# Outputs.net
KiCad netlist of a schematic drawn in Altium Designer
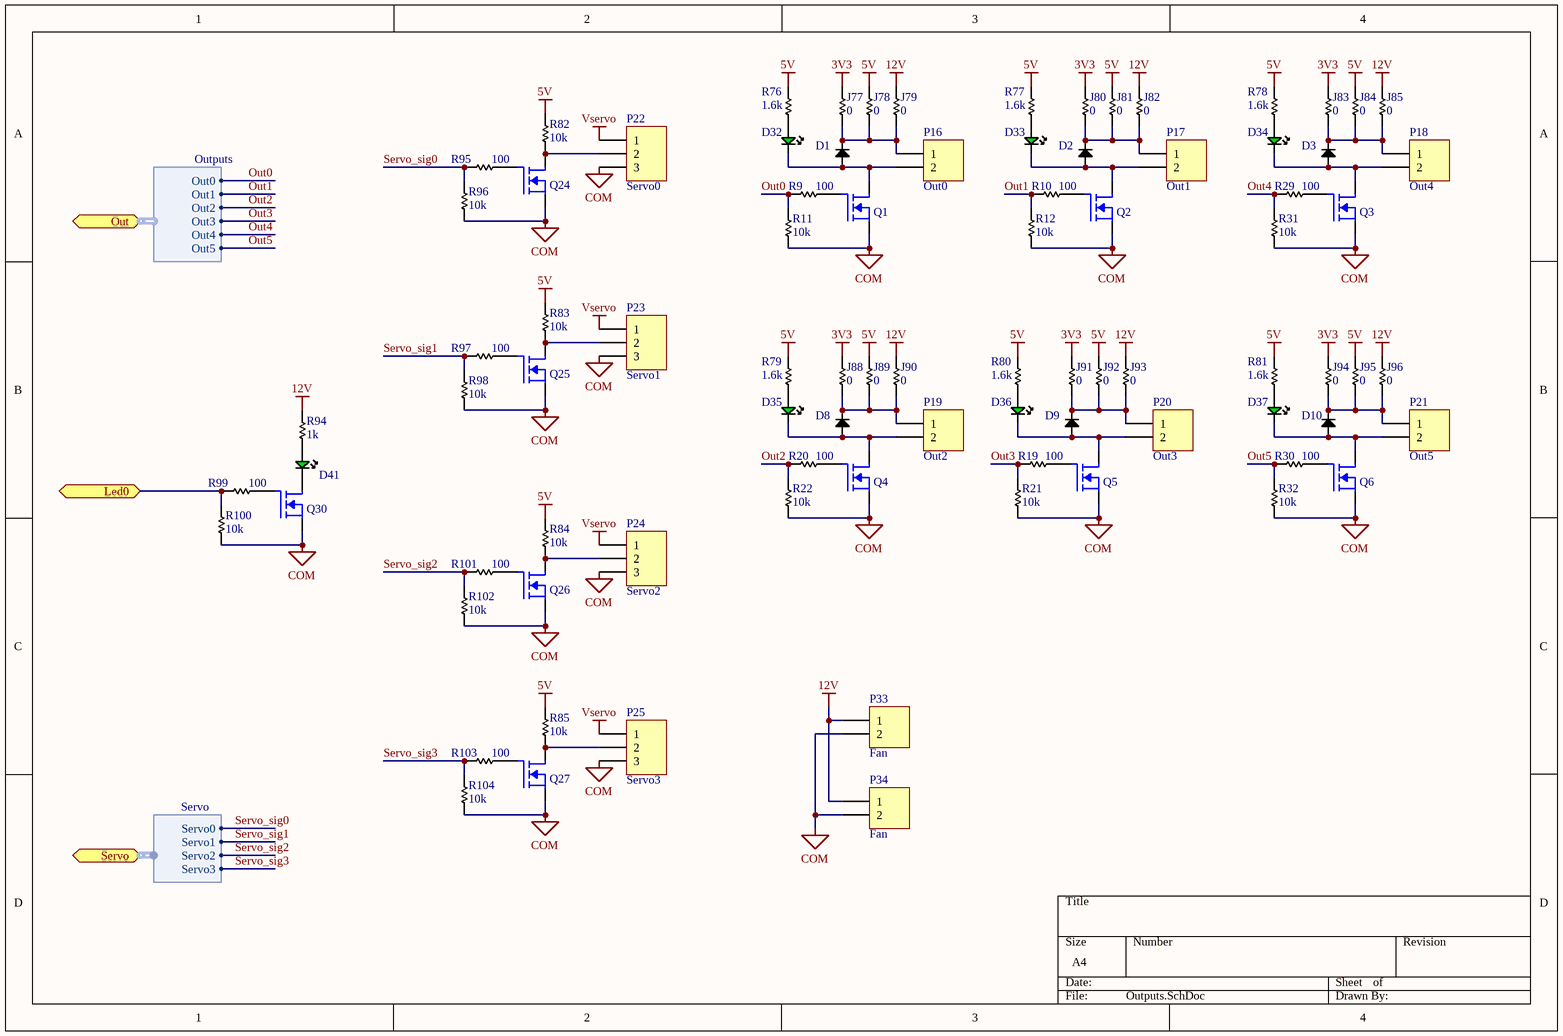
[diagram p0: Outputs.SchDoc]

(export (version "E")
  (design (tool "Eeschema 10.0.6"))
  (components
    (comp (ref "D1")
      (value "Diode")
      (footprint "DOS-214AC (SMA)")
      (description "DIODE GEN PURPOSE 1000V 1A SMA")
      (fields
        (field (name "PART NUMBER") "S1M-13-F")
        (field (name "MANUFACTURER") "Diodes Inc.")
        (field (name "CREATED BY") "Pier-Yves")
      )
      (libsource (lib "local") (part "Diode"))
    )
    (comp (ref "D2")
      (value "Diode")
      (footprint "DOS-214AC (SMA)")
      (description "DIODE GEN PURPOSE 1000V 1A SMA")
      (fields
        (field (name "PART NUMBER") "S1M-13-F")
        (field (name "MANUFACTURER") "Diodes Inc.")
        (field (name "CREATED BY") "Pier-Yves")
      )
      (libsource (lib "local") (part "Diode"))
    )
    (comp (ref "D3")
      (value "Diode")
      (footprint "DOS-214AC (SMA)")
      (description "DIODE GEN PURPOSE 1000V 1A SMA")
      (fields
        (field (name "PART NUMBER") "S1M-13-F")
        (field (name "MANUFACTURER") "Diodes Inc.")
        (field (name "CREATED BY") "Pier-Yves")
      )
      (libsource (lib "local") (part "Diode"))
    )
    (comp (ref "D8")
      (value "Diode")
      (footprint "DOS-214AC (SMA)")
      (description "DIODE GEN PURPOSE 1000V 1A SMA")
      (fields
        (field (name "PART NUMBER") "S1M-13-F")
        (field (name "MANUFACTURER") "Diodes Inc.")
        (field (name "CREATED BY") "Pier-Yves")
      )
      (libsource (lib "local") (part "Diode"))
    )
    (comp (ref "D9")
      (value "Diode")
      (footprint "DOS-214AC (SMA)")
      (description "DIODE GEN PURPOSE 1000V 1A SMA")
      (fields
        (field (name "PART NUMBER") "S1M-13-F")
        (field (name "MANUFACTURER") "Diodes Inc.")
        (field (name "CREATED BY") "Pier-Yves")
      )
      (libsource (lib "local") (part "Diode"))
    )
    (comp (ref "D10")
      (value "Diode")
      (footprint "DOS-214AC (SMA)")
      (description "DIODE GEN PURPOSE 1000V 1A SMA")
      (fields
        (field (name "PART NUMBER") "S1M-13-F")
        (field (name "MANUFACTURER") "Diodes Inc.")
        (field (name "CREATED BY") "Pier-Yves")
      )
      (libsource (lib "local") (part "Diode"))
    )
    (comp (ref "D32")
      (value "Green")
      (footprint "0603 - Led Green")
      (description "LED SMARTLED GREEN 570NM 0603")
      (fields
        (field (name "PART NUMBER") "LED-Green-2mA-lowBrigthness-0603")
        (field (name "MANUFACTURER") "OSRAM Opto Semiconductor")
        (field (name "CREATED BY") "Pier-Yves")
      )
      (libsource (lib "local") (part "Led Green"))
    )
    (comp (ref "D33")
      (value "Green")
      (footprint "0603 - Led Green")
      (description "LED SMARTLED GREEN 570NM 0603")
      (fields
        (field (name "PART NUMBER") "LED-Green-2mA-lowBrigthness-0603")
        (field (name "MANUFACTURER") "OSRAM Opto Semiconductor")
        (field (name "CREATED BY") "Pier-Yves")
      )
      (libsource (lib "local") (part "Led Green"))
    )
    (comp (ref "D34")
      (value "Green")
      (footprint "0603 - Led Green")
      (description "LED SMARTLED GREEN 570NM 0603")
      (fields
        (field (name "PART NUMBER") "LED-Green-2mA-lowBrigthness-0603")
        (field (name "MANUFACTURER") "OSRAM Opto Semiconductor")
        (field (name "CREATED BY") "Pier-Yves")
      )
      (libsource (lib "local") (part "Led Green"))
    )
    (comp (ref "D35")
      (value "Green")
      (footprint "0603 - Led Green")
      (description "LED SMARTLED GREEN 570NM 0603")
      (fields
        (field (name "PART NUMBER") "LED-Green-2mA-lowBrigthness-0603")
        (field (name "MANUFACTURER") "OSRAM Opto Semiconductor")
        (field (name "CREATED BY") "Pier-Yves")
      )
      (libsource (lib "local") (part "Led Green"))
    )
    (comp (ref "D36")
      (value "Green")
      (footprint "0603 - Led Green")
      (description "LED SMARTLED GREEN 570NM 0603")
      (fields
        (field (name "PART NUMBER") "LED-Green-2mA-lowBrigthness-0603")
        (field (name "MANUFACTURER") "OSRAM Opto Semiconductor")
        (field (name "CREATED BY") "Pier-Yves")
      )
      (libsource (lib "local") (part "Led Green"))
    )
    (comp (ref "D37")
      (value "Green")
      (footprint "0603 - Led Green")
      (description "LED SMARTLED GREEN 570NM 0603")
      (fields
        (field (name "PART NUMBER") "LED-Green-2mA-lowBrigthness-0603")
        (field (name "MANUFACTURER") "OSRAM Opto Semiconductor")
        (field (name "CREATED BY") "Pier-Yves")
      )
      (libsource (lib "local") (part "Led Green"))
    )
    (comp (ref "D41")
      (value "Green")
      (footprint "0805 - Led Green")
      (description "Led Green 0805 Low Brightness - 10mA")
      (fields
        (field (name "PART NUMBER") "LED-Green-lowBrigthness-0805")
        (field (name "MANUFACTURER") "Lite-On inc.")
        (field (name "CREATED BY") "Pier-Yves")
      )
      (libsource (lib "local") (part "Led Green"))
    )
    (comp (ref "J77")
      (value "0")
      (footprint "0805 - Resistor")
      (description "RES 0.0 OHM 1/8W JUMP 0805")
      (fields
        (field (name "PART NUMBER") "Jumper-0805")
        (field (name "MANUFACTURER") "Stackpole electronic")
        (field (name "CREATED BY") "Pier-Yves")
      )
      (libsource (lib "local") (part "Res"))
    )
    (comp (ref "J78")
      (value "0")
      (footprint "0805 - Resistor")
      (description "RES 0.0 OHM 1/8W JUMP 0805")
      (fields
        (field (name "PART NUMBER") "Jumper-0805")
        (field (name "MANUFACTURER") "Stackpole electronic")
        (field (name "CREATED BY") "Pier-Yves")
      )
      (libsource (lib "local") (part "Res"))
    )
    (comp (ref "J79")
      (value "0")
      (footprint "0805 - Resistor")
      (description "RES 0.0 OHM 1/8W JUMP 0805")
      (fields
        (field (name "PART NUMBER") "Jumper-0805")
        (field (name "MANUFACTURER") "Stackpole electronic")
        (field (name "CREATED BY") "Pier-Yves")
      )
      (libsource (lib "local") (part "Res"))
    )
    (comp (ref "J80")
      (value "0")
      (footprint "0805 - Resistor")
      (description "RES 0.0 OHM 1/8W JUMP 0805")
      (fields
        (field (name "PART NUMBER") "Jumper-0805")
        (field (name "MANUFACTURER") "Stackpole electronic")
        (field (name "CREATED BY") "Pier-Yves")
      )
      (libsource (lib "local") (part "Res"))
    )
    (comp (ref "J81")
      (value "0")
      (footprint "0805 - Resistor")
      (description "RES 0.0 OHM 1/8W JUMP 0805")
      (fields
        (field (name "PART NUMBER") "Jumper-0805")
        (field (name "MANUFACTURER") "Stackpole electronic")
        (field (name "CREATED BY") "Pier-Yves")
      )
      (libsource (lib "local") (part "Res"))
    )
    (comp (ref "J82")
      (value "0")
      (footprint "0805 - Resistor")
      (description "RES 0.0 OHM 1/8W JUMP 0805")
      (fields
        (field (name "PART NUMBER") "Jumper-0805")
        (field (name "MANUFACTURER") "Stackpole electronic")
        (field (name "CREATED BY") "Pier-Yves")
      )
      (libsource (lib "local") (part "Res"))
    )
    (comp (ref "J83")
      (value "0")
      (footprint "0805 - Resistor")
      (description "RES 0.0 OHM 1/8W JUMP 0805")
      (fields
        (field (name "PART NUMBER") "Jumper-0805")
        (field (name "MANUFACTURER") "Stackpole electronic")
        (field (name "CREATED BY") "Pier-Yves")
      )
      (libsource (lib "local") (part "Res"))
    )
    (comp (ref "J84")
      (value "0")
      (footprint "0805 - Resistor")
      (description "RES 0.0 OHM 1/8W JUMP 0805")
      (fields
        (field (name "PART NUMBER") "Jumper-0805")
        (field (name "MANUFACTURER") "Stackpole electronic")
        (field (name "CREATED BY") "Pier-Yves")
      )
      (libsource (lib "local") (part "Res"))
    )
    (comp (ref "J85")
      (value "0")
      (footprint "0805 - Resistor")
      (description "RES 0.0 OHM 1/8W JUMP 0805")
      (fields
        (field (name "PART NUMBER") "Jumper-0805")
        (field (name "MANUFACTURER") "Stackpole electronic")
        (field (name "CREATED BY") "Pier-Yves")
      )
      (libsource (lib "local") (part "Res"))
    )
    (comp (ref "J88")
      (value "0")
      (footprint "0805 - Resistor")
      (description "RES 0.0 OHM 1/8W JUMP 0805")
      (fields
        (field (name "PART NUMBER") "Jumper-0805")
        (field (name "MANUFACTURER") "Stackpole electronic")
        (field (name "CREATED BY") "Pier-Yves")
      )
      (libsource (lib "local") (part "Res"))
    )
    (comp (ref "J89")
      (value "0")
      (footprint "0805 - Resistor")
      (description "RES 0.0 OHM 1/8W JUMP 0805")
      (fields
        (field (name "PART NUMBER") "Jumper-0805")
        (field (name "MANUFACTURER") "Stackpole electronic")
        (field (name "CREATED BY") "Pier-Yves")
      )
      (libsource (lib "local") (part "Res"))
    )
    (comp (ref "J90")
      (value "0")
      (footprint "0805 - Resistor")
      (description "RES 0.0 OHM 1/8W JUMP 0805")
      (fields
        (field (name "PART NUMBER") "Jumper-0805")
        (field (name "MANUFACTURER") "Stackpole electronic")
        (field (name "CREATED BY") "Pier-Yves")
      )
      (libsource (lib "local") (part "Res"))
    )
    (comp (ref "J91")
      (value "0")
      (footprint "0805 - Resistor")
      (description "RES 0.0 OHM 1/8W JUMP 0805")
      (fields
        (field (name "PART NUMBER") "Jumper-0805")
        (field (name "MANUFACTURER") "Stackpole electronic")
        (field (name "CREATED BY") "Pier-Yves")
      )
      (libsource (lib "local") (part "Res"))
    )
    (comp (ref "J92")
      (value "0")
      (footprint "0805 - Resistor")
      (description "RES 0.0 OHM 1/8W JUMP 0805")
      (fields
        (field (name "PART NUMBER") "Jumper-0805")
        (field (name "MANUFACTURER") "Stackpole electronic")
        (field (name "CREATED BY") "Pier-Yves")
      )
      (libsource (lib "local") (part "Res"))
    )
    (comp (ref "J93")
      (value "0")
      (footprint "0805 - Resistor")
      (description "RES 0.0 OHM 1/8W JUMP 0805")
      (fields
        (field (name "PART NUMBER") "Jumper-0805")
        (field (name "MANUFACTURER") "Stackpole electronic")
        (field (name "CREATED BY") "Pier-Yves")
      )
      (libsource (lib "local") (part "Res"))
    )
    (comp (ref "J94")
      (value "0")
      (footprint "0805 - Resistor")
      (description "RES 0.0 OHM 1/8W JUMP 0805")
      (fields
        (field (name "PART NUMBER") "Jumper-0805")
        (field (name "MANUFACTURER") "Stackpole electronic")
        (field (name "CREATED BY") "Pier-Yves")
      )
      (libsource (lib "local") (part "Res"))
    )
    (comp (ref "J95")
      (value "0")
      (footprint "0805 - Resistor")
      (description "RES 0.0 OHM 1/8W JUMP 0805")
      (fields
        (field (name "PART NUMBER") "Jumper-0805")
        (field (name "MANUFACTURER") "Stackpole electronic")
        (field (name "CREATED BY") "Pier-Yves")
      )
      (libsource (lib "local") (part "Res"))
    )
    (comp (ref "J96")
      (value "0")
      (footprint "0805 - Resistor")
      (description "RES 0.0 OHM 1/8W JUMP 0805")
      (fields
        (field (name "PART NUMBER") "Jumper-0805")
        (field (name "MANUFACTURER") "Stackpole electronic")
        (field (name "CREATED BY") "Pier-Yves")
      )
      (libsource (lib "local") (part "Res"))
    )
    (comp (ref "P16")
      (value "Out0")
      (footprint "Headers - 1x2 - Vertical - Lock")
      (description "CONN HEADER 2POS .100\" STR TIN")
      (fields
        (field (name "PART NUMBER") "Header-0.100-Vertical-Lock-1X2")
        (field (name "MANUFACTURER") "Molex Inc")
        (field (name "PUBLISHER") "Altium Limited")
        (field (name "CREATED BY") "Pier-Yves")
      )
      (libsource (lib "local") (part "Header 1X2"))
    )
    (comp (ref "P17")
      (value "Out1")
      (footprint "Headers - 1x2 - Vertical - Lock")
      (description "CONN HEADER 2POS .100\" STR TIN")
      (fields
        (field (name "PART NUMBER") "Header-0.100-Vertical-Lock-1X2")
        (field (name "MANUFACTURER") "Molex Inc")
        (field (name "PUBLISHER") "Altium Limited")
        (field (name "CREATED BY") "Pier-Yves")
      )
      (libsource (lib "local") (part "Header 1X2"))
    )
    (comp (ref "P18")
      (value "Out4")
      (footprint "Headers - 1x2 - Vertical - Lock")
      (description "CONN HEADER 2POS .100\" STR TIN")
      (fields
        (field (name "PART NUMBER") "Header-0.100-Vertical-Lock-1X2")
        (field (name "MANUFACTURER") "Molex Inc")
        (field (name "PUBLISHER") "Altium Limited")
        (field (name "CREATED BY") "Pier-Yves")
      )
      (libsource (lib "local") (part "Header 1X2"))
    )
    (comp (ref "P19")
      (value "Out2")
      (footprint "Headers - 1x2 - Vertical - Lock")
      (description "CONN HEADER 2POS .100\" STR TIN")
      (fields
        (field (name "PART NUMBER") "Header-0.100-Vertical-Lock-1X2")
        (field (name "MANUFACTURER") "Molex Inc")
        (field (name "PUBLISHER") "Altium Limited")
        (field (name "CREATED BY") "Pier-Yves")
      )
      (libsource (lib "local") (part "Header 1X2"))
    )
    (comp (ref "P20")
      (value "Out3")
      (footprint "Headers - 1x2 - Vertical - Lock")
      (description "CONN HEADER 2POS .100\" STR TIN")
      (fields
        (field (name "PART NUMBER") "Header-0.100-Vertical-Lock-1X2")
        (field (name "MANUFACTURER") "Molex Inc")
        (field (name "PUBLISHER") "Altium Limited")
        (field (name "CREATED BY") "Pier-Yves")
      )
      (libsource (lib "local") (part "Header 1X2"))
    )
    (comp (ref "P21")
      (value "Out5")
      (footprint "Headers - 1x2 - Vertical - Lock")
      (description "CONN HEADER 2POS .100\" STR TIN")
      (fields
        (field (name "PART NUMBER") "Header-0.100-Vertical-Lock-1X2")
        (field (name "MANUFACTURER") "Molex Inc")
        (field (name "PUBLISHER") "Altium Limited")
        (field (name "CREATED BY") "Pier-Yves")
      )
      (libsource (lib "local") (part "Header 1X2"))
    )
    (comp (ref "P22")
      (value "Servo0")
      (footprint "Headers - 1x3 - Vertical - Lock")
      (description "CONN HEADER 3POS .100\" STR TIN")
      (fields
        (field (name "PART NUMBER") "Header-0.100-Vertical-Lock-1X3")
        (field (name "MANUFACTURER") "Molex Inc")
        (field (name "PUBLISHER") "Altium Limited")
        (field (name "CREATED BY") "Pier-Yves")
      )
      (libsource (lib "local") (part "Header 1X3"))
    )
    (comp (ref "P23")
      (value "Servo1")
      (footprint "Headers - 1x3 - Vertical - Lock")
      (description "CONN HEADER 3POS .100\" STR TIN")
      (fields
        (field (name "PART NUMBER") "Header-0.100-Vertical-Lock-1X3")
        (field (name "MANUFACTURER") "Molex Inc")
        (field (name "PUBLISHER") "Altium Limited")
        (field (name "CREATED BY") "Pier-Yves")
      )
      (libsource (lib "local") (part "Header 1X3"))
    )
    (comp (ref "P24")
      (value "Servo2")
      (footprint "Headers - 1x3 - Vertical - Lock")
      (description "CONN HEADER 3POS .100\" STR TIN")
      (fields
        (field (name "PART NUMBER") "Header-0.100-Vertical-Lock-1X3")
        (field (name "MANUFACTURER") "Molex Inc")
        (field (name "PUBLISHER") "Altium Limited")
        (field (name "CREATED BY") "Pier-Yves")
      )
      (libsource (lib "local") (part "Header 1X3"))
    )
    (comp (ref "P25")
      (value "Servo3")
      (footprint "Headers - 1x3 - Vertical - Lock")
      (description "CONN HEADER 3POS .100\" STR TIN")
      (fields
        (field (name "PART NUMBER") "Header-0.100-Vertical-Lock-1X3")
        (field (name "MANUFACTURER") "Molex Inc")
        (field (name "PUBLISHER") "Altium Limited")
        (field (name "CREATED BY") "Pier-Yves")
      )
      (libsource (lib "local") (part "Header 1X3"))
    )
    (comp (ref "P33")
      (value "Fan")
      (footprint "Headers - 1x2 - Vertical - Lock")
      (description "CONN HEADER 2POS .100\" STR TIN")
      (fields
        (field (name "PART NUMBER") "Header-0.100-Vertical-Lock-1X2")
        (field (name "MANUFACTURER") "Molex Inc")
        (field (name "PUBLISHER") "Altium Limited")
        (field (name "CREATED BY") "Pier-Yves")
      )
      (libsource (lib "local") (part "Header 1X2"))
    )
    (comp (ref "P34")
      (value "Fan")
      (footprint "Headers - 1x2 - Vertical - Lock")
      (description "CONN HEADER 2POS .100\" STR TIN")
      (fields
        (field (name "PART NUMBER") "Header-0.100-Vertical-Lock-1X2")
        (field (name "MANUFACTURER") "Molex Inc")
        (field (name "PUBLISHER") "Altium Limited")
        (field (name "CREATED BY") "Pier-Yves")
      )
      (libsource (lib "local") (part "Header 1X2"))
    )
    (comp (ref "Q1")
      (value "MOSFET_N")
      (footprint "SOT23-3")
      (description "MosFET Channel-N SOT-23-3 3.3A")
      (fields
        (field (name "PART NUMBER") "2N7002")
        (field (name "MANUFACTURER") "Vishay Siliconix")
        (field (name "CREATED BY") "Pier-Yves")
      )
      (libsource (lib "local") (part "MOSFET_N_GSD"))
    )
    (comp (ref "Q2")
      (value "MOSFET_N")
      (footprint "SOT23-3")
      (description "MosFET Channel-N SOT-23-3 3.3A")
      (fields
        (field (name "PART NUMBER") "2N7002")
        (field (name "MANUFACTURER") "Vishay Siliconix")
        (field (name "CREATED BY") "Pier-Yves")
      )
      (libsource (lib "local") (part "MOSFET_N_GSD"))
    )
    (comp (ref "Q3")
      (value "MOSFET_N")
      (footprint "SOT23-3")
      (description "MosFET Channel-N SOT-23-3 3.3A")
      (fields
        (field (name "PART NUMBER") "2N7002")
        (field (name "MANUFACTURER") "Vishay Siliconix")
        (field (name "CREATED BY") "Pier-Yves")
      )
      (libsource (lib "local") (part "MOSFET_N_GSD"))
    )
    (comp (ref "Q4")
      (value "MOSFET_N")
      (footprint "SOT23-3")
      (description "MosFET Channel-N SOT-23-3 3.3A")
      (fields
        (field (name "PART NUMBER") "2N7002")
        (field (name "MANUFACTURER") "Vishay Siliconix")
        (field (name "CREATED BY") "Pier-Yves")
      )
      (libsource (lib "local") (part "MOSFET_N_GSD"))
    )
    (comp (ref "Q5")
      (value "MOSFET_N")
      (footprint "SOT23-3")
      (description "MosFET Channel-N SOT-23-3 3.3A")
      (fields
        (field (name "PART NUMBER") "2N7002")
        (field (name "MANUFACTURER") "Vishay Siliconix")
        (field (name "CREATED BY") "Pier-Yves")
      )
      (libsource (lib "local") (part "MOSFET_N_GSD"))
    )
    (comp (ref "Q6")
      (value "MOSFET_N")
      (footprint "SOT23-3")
      (description "MosFET Channel-N SOT-23-3 3.3A")
      (fields
        (field (name "PART NUMBER") "2N7002")
        (field (name "MANUFACTURER") "Vishay Siliconix")
        (field (name "CREATED BY") "Pier-Yves")
      )
      (libsource (lib "local") (part "MOSFET_N_GSD"))
    )
    (comp (ref "Q24")
      (value "MOSFET_N")
      (footprint "SOT23-3")
      (description "MosFET Channel-N SOT-23-3 3.3A")
      (fields
        (field (name "PART NUMBER") "2N7002")
        (field (name "MANUFACTURER") "Vishay Siliconix")
        (field (name "CREATED BY") "Pier-Yves")
      )
      (libsource (lib "local") (part "MOSFET_N_GSD"))
    )
    (comp (ref "Q25")
      (value "MOSFET_N")
      (footprint "SOT23-3")
      (description "MosFET Channel-N SOT-23-3 3.3A")
      (fields
        (field (name "PART NUMBER") "2N7002")
        (field (name "MANUFACTURER") "Vishay Siliconix")
        (field (name "CREATED BY") "Pier-Yves")
      )
      (libsource (lib "local") (part "MOSFET_N_GSD"))
    )
    (comp (ref "Q26")
      (value "MOSFET_N")
      (footprint "SOT23-3")
      (description "MosFET Channel-N SOT-23-3 3.3A")
      (fields
        (field (name "PART NUMBER") "2N7002")
        (field (name "MANUFACTURER") "Vishay Siliconix")
        (field (name "CREATED BY") "Pier-Yves")
      )
      (libsource (lib "local") (part "MOSFET_N_GSD"))
    )
    (comp (ref "Q27")
      (value "MOSFET_N")
      (footprint "SOT23-3")
      (description "MosFET Channel-N SOT-23-3 3.3A")
      (fields
        (field (name "PART NUMBER") "2N7002")
        (field (name "MANUFACTURER") "Vishay Siliconix")
        (field (name "CREATED BY") "Pier-Yves")
      )
      (libsource (lib "local") (part "MOSFET_N_GSD"))
    )
    (comp (ref "Q30")
      (value "MOSFET_N")
      (footprint "SOT23-3")
      (description "MosFET Channel-N SOT-23-3 3.3A")
      (fields
        (field (name "PART NUMBER") "2N7002")
        (field (name "MANUFACTURER") "Vishay Siliconix")
        (field (name "CREATED BY") "Pier-Yves")
      )
      (libsource (lib "local") (part "MOSFET_N_GSD"))
    )
    (comp (ref "R9")
      (value "100")
      (footprint "0805 - Resistor")
      (description "RES 100 OHM 1/8W 5% 0805 SMD")
      (fields
        (field (name "PART NUMBER") "Yagao-RC0805-100")
        (field (name "MANUFACTURER") "Yagao")
        (field (name "CREATED BY") "Pier-Yves")
      )
      (libsource (lib "local") (part "Res"))
    )
    (comp (ref "R10")
      (value "100")
      (footprint "0805 - Resistor")
      (description "RES 100 OHM 1/8W 5% 0805 SMD")
      (fields
        (field (name "PART NUMBER") "Yagao-RC0805-100")
        (field (name "MANUFACTURER") "Yagao")
        (field (name "CREATED BY") "Pier-Yves")
      )
      (libsource (lib "local") (part "Res"))
    )
    (comp (ref "R11")
      (value "10k")
      (footprint "0805 - Resistor")
      (description "RES 10K OHM 1/8W 5% 0805 SMD")
      (fields
        (field (name "PART NUMBER") "Yagao-RC0805-10k")
        (field (name "MANUFACTURER") "Yagao")
        (field (name "CREATED BY") "Pier-Yves")
      )
      (libsource (lib "local") (part "Res"))
    )
    (comp (ref "R12")
      (value "10k")
      (footprint "0805 - Resistor")
      (description "RES 10K OHM 1/8W 5% 0805 SMD")
      (fields
        (field (name "PART NUMBER") "Yagao-RC0805-10k")
        (field (name "MANUFACTURER") "Yagao")
        (field (name "CREATED BY") "Pier-Yves")
      )
      (libsource (lib "local") (part "Res"))
    )
    (comp (ref "R19")
      (value "100")
      (footprint "0805 - Resistor")
      (description "RES 100 OHM 1/8W 5% 0805 SMD")
      (fields
        (field (name "PART NUMBER") "Yagao-RC0805-100")
        (field (name "MANUFACTURER") "Yagao")
        (field (name "CREATED BY") "Pier-Yves")
      )
      (libsource (lib "local") (part "Res"))
    )
    (comp (ref "R20")
      (value "100")
      (footprint "0805 - Resistor")
      (description "RES 100 OHM 1/8W 5% 0805 SMD")
      (fields
        (field (name "PART NUMBER") "Yagao-RC0805-100")
        (field (name "MANUFACTURER") "Yagao")
        (field (name "CREATED BY") "Pier-Yves")
      )
      (libsource (lib "local") (part "Res"))
    )
    (comp (ref "R21")
      (value "10k")
      (footprint "0805 - Resistor")
      (description "RES 10K OHM 1/8W 5% 0805 SMD")
      (fields
        (field (name "PART NUMBER") "Yagao-RC0805-10k")
        (field (name "MANUFACTURER") "Yagao")
        (field (name "CREATED BY") "Pier-Yves")
      )
      (libsource (lib "local") (part "Res"))
    )
    (comp (ref "R22")
      (value "10k")
      (footprint "0805 - Resistor")
      (description "RES 10K OHM 1/8W 5% 0805 SMD")
      (fields
        (field (name "PART NUMBER") "Yagao-RC0805-10k")
        (field (name "MANUFACTURER") "Yagao")
        (field (name "CREATED BY") "Pier-Yves")
      )
      (libsource (lib "local") (part "Res"))
    )
    (comp (ref "R29")
      (value "100")
      (footprint "0805 - Resistor")
      (description "RES 100 OHM 1/8W 5% 0805 SMD")
      (fields
        (field (name "PART NUMBER") "Yagao-RC0805-100")
        (field (name "MANUFACTURER") "Yagao")
        (field (name "CREATED BY") "Pier-Yves")
      )
      (libsource (lib "local") (part "Res"))
    )
    (comp (ref "R30")
      (value "100")
      (footprint "0805 - Resistor")
      (description "RES 100 OHM 1/8W 5% 0805 SMD")
      (fields
        (field (name "PART NUMBER") "Yagao-RC0805-100")
        (field (name "MANUFACTURER") "Yagao")
        (field (name "CREATED BY") "Pier-Yves")
      )
      (libsource (lib "local") (part "Res"))
    )
    (comp (ref "R31")
      (value "10k")
      (footprint "0805 - Resistor")
      (description "RES 10K OHM 1/8W 5% 0805 SMD")
      (fields
        (field (name "PART NUMBER") "Yagao-RC0805-10k")
        (field (name "MANUFACTURER") "Yagao")
        (field (name "CREATED BY") "Pier-Yves")
      )
      (libsource (lib "local") (part "Res"))
    )
    (comp (ref "R32")
      (value "10k")
      (footprint "0805 - Resistor")
      (description "RES 10K OHM 1/8W 5% 0805 SMD")
      (fields
        (field (name "PART NUMBER") "Yagao-RC0805-10k")
        (field (name "MANUFACTURER") "Yagao")
        (field (name "CREATED BY") "Pier-Yves")
      )
      (libsource (lib "local") (part "Res"))
    )
    (comp (ref "R76")
      (value "1.6k")
      (footprint "0805 - Resistor")
      (description "RES 1.6K OHM 1/8W 5% 0805 SMD")
      (fields
        (field (name "PART NUMBER") "Yagao-RC0805-1.6k")
        (field (name "MANUFACTURER") "Yagao")
        (field (name "CREATED BY") "Pier-Yves")
      )
      (libsource (lib "local") (part "Res"))
    )
    (comp (ref "R77")
      (value "1.6k")
      (footprint "0805 - Resistor")
      (description "RES 1.6K OHM 1/8W 5% 0805 SMD")
      (fields
        (field (name "PART NUMBER") "Yagao-RC0805-1.6k")
        (field (name "MANUFACTURER") "Yagao")
        (field (name "CREATED BY") "Pier-Yves")
      )
      (libsource (lib "local") (part "Res"))
    )
    (comp (ref "R78")
      (value "1.6k")
      (footprint "0805 - Resistor")
      (description "RES 1.6K OHM 1/8W 5% 0805 SMD")
      (fields
        (field (name "PART NUMBER") "Yagao-RC0805-1.6k")
        (field (name "MANUFACTURER") "Yagao")
        (field (name "CREATED BY") "Pier-Yves")
      )
      (libsource (lib "local") (part "Res"))
    )
    (comp (ref "R79")
      (value "1.6k")
      (footprint "0805 - Resistor")
      (description "RES 1.6K OHM 1/8W 5% 0805 SMD")
      (fields
        (field (name "PART NUMBER") "Yagao-RC0805-1.6k")
        (field (name "MANUFACTURER") "Yagao")
        (field (name "CREATED BY") "Pier-Yves")
      )
      (libsource (lib "local") (part "Res"))
    )
    (comp (ref "R80")
      (value "1.6k")
      (footprint "0805 - Resistor")
      (description "RES 1.6K OHM 1/8W 5% 0805 SMD")
      (fields
        (field (name "PART NUMBER") "Yagao-RC0805-1.6k")
        (field (name "MANUFACTURER") "Yagao")
        (field (name "CREATED BY") "Pier-Yves")
      )
      (libsource (lib "local") (part "Res"))
    )
    (comp (ref "R81")
      (value "1.6k")
      (footprint "0805 - Resistor")
      (description "RES 1.6K OHM 1/8W 5% 0805 SMD")
      (fields
        (field (name "PART NUMBER") "Yagao-RC0805-1.6k")
        (field (name "MANUFACTURER") "Yagao")
        (field (name "CREATED BY") "Pier-Yves")
      )
      (libsource (lib "local") (part "Res"))
    )
    (comp (ref "R82")
      (value "10k")
      (footprint "0805 - Resistor")
      (description "RES 10K OHM 1/8W 5% 0805 SMD")
      (fields
        (field (name "PART NUMBER") "Yagao-RC0805-10k")
        (field (name "MANUFACTURER") "Yagao")
        (field (name "CREATED BY") "Pier-Yves")
      )
      (libsource (lib "local") (part "Res"))
    )
    (comp (ref "R83")
      (value "10k")
      (footprint "0805 - Resistor")
      (description "RES 10K OHM 1/8W 5% 0805 SMD")
      (fields
        (field (name "PART NUMBER") "Yagao-RC0805-10k")
        (field (name "MANUFACTURER") "Yagao")
        (field (name "CREATED BY") "Pier-Yves")
      )
      (libsource (lib "local") (part "Res"))
    )
    (comp (ref "R84")
      (value "10k")
      (footprint "0805 - Resistor")
      (description "RES 10K OHM 1/8W 5% 0805 SMD")
      (fields
        (field (name "PART NUMBER") "Yagao-RC0805-10k")
        (field (name "MANUFACTURER") "Yagao")
        (field (name "CREATED BY") "Pier-Yves")
      )
      (libsource (lib "local") (part "Res"))
    )
    (comp (ref "R85")
      (value "10k")
      (footprint "0805 - Resistor")
      (description "RES 10K OHM 1/8W 5% 0805 SMD")
      (fields
        (field (name "PART NUMBER") "Yagao-RC0805-10k")
        (field (name "MANUFACTURER") "Yagao")
        (field (name "CREATED BY") "Pier-Yves")
      )
      (libsource (lib "local") (part "Res"))
    )
    (comp (ref "R94")
      (value "1k")
      (footprint "0805 - Resistor")
      (description "RES 1.0K OHM 1/8W 5% 0805 SMD")
      (fields
        (field (name "PART NUMBER") "Yagao-RC0805-1k")
        (field (name "MANUFACTURER") "Yagao")
        (field (name "CREATED BY") "Pier-Yves")
      )
      (libsource (lib "local") (part "Res"))
    )
    (comp (ref "R95")
      (value "100")
      (footprint "0805 - Resistor")
      (description "RES 100 OHM 1/8W 5% 0805 SMD")
      (fields
        (field (name "PART NUMBER") "Yagao-RC0805-100")
        (field (name "MANUFACTURER") "Yagao")
        (field (name "CREATED BY") "Pier-Yves")
      )
      (libsource (lib "local") (part "Res"))
    )
    (comp (ref "R96")
      (value "10k")
      (footprint "0805 - Resistor")
      (description "RES 10K OHM 1/8W 5% 0805 SMD")
      (fields
        (field (name "PART NUMBER") "Yagao-RC0805-10k")
        (field (name "MANUFACTURER") "Yagao")
        (field (name "CREATED BY") "Pier-Yves")
      )
      (libsource (lib "local") (part "Res"))
    )
    (comp (ref "R97")
      (value "100")
      (footprint "0805 - Resistor")
      (description "RES 100 OHM 1/8W 5% 0805 SMD")
      (fields
        (field (name "PART NUMBER") "Yagao-RC0805-100")
        (field (name "MANUFACTURER") "Yagao")
        (field (name "CREATED BY") "Pier-Yves")
      )
      (libsource (lib "local") (part "Res"))
    )
    (comp (ref "R98")
      (value "10k")
      (footprint "0805 - Resistor")
      (description "RES 10K OHM 1/8W 5% 0805 SMD")
      (fields
        (field (name "PART NUMBER") "Yagao-RC0805-10k")
        (field (name "MANUFACTURER") "Yagao")
        (field (name "CREATED BY") "Pier-Yves")
      )
      (libsource (lib "local") (part "Res"))
    )
    (comp (ref "R99")
      (value "100")
      (footprint "0805 - Resistor")
      (description "RES 100 OHM 1/8W 5% 0805 SMD")
      (fields
        (field (name "PART NUMBER") "Yagao-RC0805-100")
        (field (name "MANUFACTURER") "Yagao")
        (field (name "CREATED BY") "Pier-Yves")
      )
      (libsource (lib "local") (part "Res"))
    )
    (comp (ref "R100")
      (value "10k")
      (footprint "0805 - Resistor")
      (description "RES 10K OHM 1/8W 5% 0805 SMD")
      (fields
        (field (name "PART NUMBER") "Yagao-RC0805-10k")
        (field (name "MANUFACTURER") "Yagao")
        (field (name "CREATED BY") "Pier-Yves")
      )
      (libsource (lib "local") (part "Res"))
    )
    (comp (ref "R101")
      (value "100")
      (footprint "0805 - Resistor")
      (description "RES 100 OHM 1/8W 5% 0805 SMD")
      (fields
        (field (name "PART NUMBER") "Yagao-RC0805-100")
        (field (name "MANUFACTURER") "Yagao")
        (field (name "CREATED BY") "Pier-Yves")
      )
      (libsource (lib "local") (part "Res"))
    )
    (comp (ref "R102")
      (value "10k")
      (footprint "0805 - Resistor")
      (description "RES 10K OHM 1/8W 5% 0805 SMD")
      (fields
        (field (name "PART NUMBER") "Yagao-RC0805-10k")
        (field (name "MANUFACTURER") "Yagao")
        (field (name "CREATED BY") "Pier-Yves")
      )
      (libsource (lib "local") (part "Res"))
    )
    (comp (ref "R103")
      (value "100")
      (footprint "0805 - Resistor")
      (description "RES 100 OHM 1/8W 5% 0805 SMD")
      (fields
        (field (name "PART NUMBER") "Yagao-RC0805-100")
        (field (name "MANUFACTURER") "Yagao")
        (field (name "CREATED BY") "Pier-Yves")
      )
      (libsource (lib "local") (part "Res"))
    )
    (comp (ref "R104")
      (value "10k")
      (footprint "0805 - Resistor")
      (description "RES 10K OHM 1/8W 5% 0805 SMD")
      (fields
        (field (name "PART NUMBER") "Yagao-RC0805-10k")
        (field (name "MANUFACTURER") "Yagao")
        (field (name "CREATED BY") "Pier-Yves")
      )
      (libsource (lib "local") (part "Res"))
    )
  )
  (nets
    (net (code "3") (name "/Led0") (class "Default")
      (node (ref "R100") (pin "2") (pinfunction "2_2") (pintype "passive"))
      (node (ref "R99") (pin "1") (pinfunction "1_1") (pintype "passive"))
    )
    (net (code "4") (name "/Out0") (class "Default")
      (node (ref "R11") (pin "2") (pinfunction "2_2") (pintype "passive"))
      (node (ref "R9") (pin "1") (pinfunction "1_1") (pintype "passive"))
    )
    (net (code "5") (name "/Out1") (class "Default")
      (node (ref "R10") (pin "1") (pinfunction "1_1") (pintype "passive"))
      (node (ref "R12") (pin "2") (pinfunction "2_2") (pintype "passive"))
    )
    (net (code "6") (name "/Out2") (class "Default")
      (node (ref "R20") (pin "1") (pinfunction "1_1") (pintype "passive"))
      (node (ref "R22") (pin "2") (pinfunction "2_2") (pintype "passive"))
    )
    (net (code "7") (name "/Out3") (class "Default")
      (node (ref "R19") (pin "1") (pinfunction "1_1") (pintype "passive"))
      (node (ref "R21") (pin "2") (pinfunction "2_2") (pintype "passive"))
    )
    (net (code "8") (name "/Out4") (class "Default")
      (node (ref "R29") (pin "1") (pinfunction "1_1") (pintype "passive"))
      (node (ref "R31") (pin "2") (pinfunction "2_2") (pintype "passive"))
    )
    (net (code "9") (name "/Out5") (class "Default")
      (node (ref "R30") (pin "1") (pinfunction "1_1") (pintype "passive"))
      (node (ref "R32") (pin "2") (pinfunction "2_2") (pintype "passive"))
    )
    (net (code "10") (name "/Servo_sig0") (class "Default")
      (node (ref "R95") (pin "1") (pinfunction "1_1") (pintype "passive"))
      (node (ref "R96") (pin "2") (pinfunction "2_2") (pintype "passive"))
    )
    (net (code "11") (name "/Servo_sig1") (class "Default")
      (node (ref "R97") (pin "1") (pinfunction "1_1") (pintype "passive"))
      (node (ref "R98") (pin "2") (pinfunction "2_2") (pintype "passive"))
    )
    (net (code "12") (name "/Servo_sig2") (class "Default")
      (node (ref "R101") (pin "1") (pinfunction "1_1") (pintype "passive"))
      (node (ref "R102") (pin "2") (pinfunction "2_2") (pintype "passive"))
    )
    (net (code "13") (name "/Servo_sig3") (class "Default")
      (node (ref "R103") (pin "1") (pinfunction "1_1") (pintype "passive"))
      (node (ref "R104") (pin "2") (pinfunction "2_2") (pintype "passive"))
    )
    (net (code "16") (name "3V3") (class "Default")
      (node (ref "J77") (pin "2") (pinfunction "2_2") (pintype "passive"))
      (node (ref "J80") (pin "2") (pinfunction "2_2") (pintype "passive"))
      (node (ref "J83") (pin "2") (pinfunction "2_2") (pintype "passive"))
      (node (ref "J88") (pin "2") (pinfunction "2_2") (pintype "passive"))
      (node (ref "J91") (pin "2") (pinfunction "2_2") (pintype "passive"))
      (node (ref "J94") (pin "2") (pinfunction "2_2") (pintype "passive"))
    )
    (net (code "17") (name "5V") (class "Default")
      (node (ref "J78") (pin "2") (pinfunction "2_2") (pintype "passive"))
      (node (ref "J81") (pin "2") (pinfunction "2_2") (pintype "passive"))
      (node (ref "J84") (pin "2") (pinfunction "2_2") (pintype "passive"))
      (node (ref "J89") (pin "2") (pinfunction "2_2") (pintype "passive"))
      (node (ref "J92") (pin "2") (pinfunction "2_2") (pintype "passive"))
      (node (ref "J95") (pin "2") (pinfunction "2_2") (pintype "passive"))
      (node (ref "R76") (pin "2") (pinfunction "2_2") (pintype "passive"))
      (node (ref "R77") (pin "2") (pinfunction "2_2") (pintype "passive"))
      (node (ref "R78") (pin "2") (pinfunction "2_2") (pintype "passive"))
      (node (ref "R79") (pin "2") (pinfunction "2_2") (pintype "passive"))
      (node (ref "R80") (pin "2") (pinfunction "2_2") (pintype "passive"))
      (node (ref "R81") (pin "2") (pinfunction "2_2") (pintype "passive"))
      (node (ref "R82") (pin "2") (pinfunction "2_2") (pintype "passive"))
      (node (ref "R83") (pin "2") (pinfunction "2_2") (pintype "passive"))
      (node (ref "R84") (pin "2") (pinfunction "2_2") (pintype "passive"))
      (node (ref "R85") (pin "2") (pinfunction "2_2") (pintype "passive"))
    )
    (net (code "18") (name "12V") (class "Default")
      (node (ref "J79") (pin "2") (pinfunction "2_2") (pintype "passive"))
      (node (ref "J82") (pin "2") (pinfunction "2_2") (pintype "passive"))
      (node (ref "J85") (pin "2") (pinfunction "2_2") (pintype "passive"))
      (node (ref "J90") (pin "2") (pinfunction "2_2") (pintype "passive"))
      (node (ref "J93") (pin "2") (pinfunction "2_2") (pintype "passive"))
      (node (ref "J96") (pin "2") (pinfunction "2_2") (pintype "passive"))
      (node (ref "P33") (pin "1") (pinfunction "1_1") (pintype "passive"))
      (node (ref "P34") (pin "1") (pinfunction "1_1") (pintype "passive"))
      (node (ref "R94") (pin "1") (pinfunction "1_1") (pintype "passive"))
    )
    (net (code "19") (name "COM") (class "Default")
      (node (ref "P22") (pin "3") (pinfunction "3_3") (pintype "passive"))
      (node (ref "P23") (pin "3") (pinfunction "3_3") (pintype "passive"))
      (node (ref "P24") (pin "3") (pinfunction "3_3") (pintype "passive"))
      (node (ref "P25") (pin "3") (pinfunction "3_3") (pintype "passive"))
      (node (ref "P33") (pin "2") (pinfunction "2_2") (pintype "passive"))
      (node (ref "P34") (pin "2") (pinfunction "2_2") (pintype "passive"))
      (node (ref "Q1") (pin "2") (pinfunction "S_2") (pintype "passive"))
      (node (ref "Q2") (pin "2") (pinfunction "S_2") (pintype "passive"))
      (node (ref "Q24") (pin "2") (pinfunction "S_2") (pintype "passive"))
      (node (ref "Q25") (pin "2") (pinfunction "S_2") (pintype "passive"))
      (node (ref "Q26") (pin "2") (pinfunction "S_2") (pintype "passive"))
      (node (ref "Q27") (pin "2") (pinfunction "S_2") (pintype "passive"))
      (node (ref "Q3") (pin "2") (pinfunction "S_2") (pintype "passive"))
      (node (ref "Q30") (pin "2") (pinfunction "S_2") (pintype "passive"))
      (node (ref "Q4") (pin "2") (pinfunction "S_2") (pintype "passive"))
      (node (ref "Q5") (pin "2") (pinfunction "S_2") (pintype "passive"))
      (node (ref "Q6") (pin "2") (pinfunction "S_2") (pintype "passive"))
      (node (ref "R100") (pin "1") (pinfunction "1_1") (pintype "passive"))
      (node (ref "R102") (pin "1") (pinfunction "1_1") (pintype "passive"))
      (node (ref "R104") (pin "1") (pinfunction "1_1") (pintype "passive"))
      (node (ref "R11") (pin "1") (pinfunction "1_1") (pintype "passive"))
      (node (ref "R12") (pin "1") (pinfunction "1_1") (pintype "passive"))
      (node (ref "R21") (pin "1") (pinfunction "1_1") (pintype "passive"))
      (node (ref "R22") (pin "1") (pinfunction "1_1") (pintype "passive"))
      (node (ref "R31") (pin "1") (pinfunction "1_1") (pintype "passive"))
      (node (ref "R32") (pin "1") (pinfunction "1_1") (pintype "passive"))
      (node (ref "R96") (pin "1") (pinfunction "1_1") (pintype "passive"))
      (node (ref "R98") (pin "1") (pinfunction "1_1") (pintype "passive"))
    )
    (net (code "20") (name "Net-(D1-A)") (class "Default")
      (node (ref "D1") (pin "1") (pinfunction "A_1") (pintype "passive"))
      (node (ref "D32") (pin "2") (pinfunction "K_2") (pintype "passive"))
      (node (ref "P16") (pin "2") (pinfunction "2_2") (pintype "passive"))
      (node (ref "Q1") (pin "3") (pinfunction "D_3") (pintype "passive"))
    )
    (net (code "21") (name "Net-(D1-K)") (class "Default")
      (node (ref "D1") (pin "2") (pinfunction "K_2") (pintype "passive"))
      (node (ref "J77") (pin "1") (pinfunction "1_1") (pintype "passive"))
      (node (ref "J78") (pin "1") (pinfunction "1_1") (pintype "passive"))
      (node (ref "J79") (pin "1") (pinfunction "1_1") (pintype "passive"))
      (node (ref "P16") (pin "1") (pinfunction "1_1") (pintype "passive"))
    )
    (net (code "22") (name "Net-(D2-A)") (class "Default")
      (node (ref "D2") (pin "1") (pinfunction "A_1") (pintype "passive"))
      (node (ref "D33") (pin "2") (pinfunction "K_2") (pintype "passive"))
      (node (ref "P17") (pin "2") (pinfunction "2_2") (pintype "passive"))
      (node (ref "Q2") (pin "3") (pinfunction "D_3") (pintype "passive"))
    )
    (net (code "23") (name "Net-(D2-K)") (class "Default")
      (node (ref "D2") (pin "2") (pinfunction "K_2") (pintype "passive"))
      (node (ref "J80") (pin "1") (pinfunction "1_1") (pintype "passive"))
      (node (ref "J81") (pin "1") (pinfunction "1_1") (pintype "passive"))
      (node (ref "J82") (pin "1") (pinfunction "1_1") (pintype "passive"))
      (node (ref "P17") (pin "1") (pinfunction "1_1") (pintype "passive"))
    )
    (net (code "24") (name "Net-(D3-A)") (class "Default")
      (node (ref "D3") (pin "1") (pinfunction "A_1") (pintype "passive"))
      (node (ref "D34") (pin "2") (pinfunction "K_2") (pintype "passive"))
      (node (ref "P18") (pin "2") (pinfunction "2_2") (pintype "passive"))
      (node (ref "Q3") (pin "3") (pinfunction "D_3") (pintype "passive"))
    )
    (net (code "25") (name "Net-(D3-K)") (class "Default")
      (node (ref "D3") (pin "2") (pinfunction "K_2") (pintype "passive"))
      (node (ref "J83") (pin "1") (pinfunction "1_1") (pintype "passive"))
      (node (ref "J84") (pin "1") (pinfunction "1_1") (pintype "passive"))
      (node (ref "J85") (pin "1") (pinfunction "1_1") (pintype "passive"))
      (node (ref "P18") (pin "1") (pinfunction "1_1") (pintype "passive"))
    )
    (net (code "26") (name "Net-(D8-K)") (class "Default")
      (node (ref "D8") (pin "2") (pinfunction "K_2") (pintype "passive"))
      (node (ref "J88") (pin "1") (pinfunction "1_1") (pintype "passive"))
      (node (ref "J89") (pin "1") (pinfunction "1_1") (pintype "passive"))
      (node (ref "J90") (pin "1") (pinfunction "1_1") (pintype "passive"))
      (node (ref "P19") (pin "1") (pinfunction "1_1") (pintype "passive"))
    )
    (net (code "27") (name "Net-(D9-K)") (class "Default")
      (node (ref "D9") (pin "2") (pinfunction "K_2") (pintype "passive"))
      (node (ref "J91") (pin "1") (pinfunction "1_1") (pintype "passive"))
      (node (ref "J92") (pin "1") (pinfunction "1_1") (pintype "passive"))
      (node (ref "J93") (pin "1") (pinfunction "1_1") (pintype "passive"))
      (node (ref "P20") (pin "1") (pinfunction "1_1") (pintype "passive"))
    )
    (net (code "28") (name "Net-(D10-A)") (class "Default")
      (node (ref "D10") (pin "1") (pinfunction "A_1") (pintype "passive"))
      (node (ref "D37") (pin "2") (pinfunction "K_2") (pintype "passive"))
      (node (ref "P21") (pin "2") (pinfunction "2_2") (pintype "passive"))
      (node (ref "Q6") (pin "3") (pinfunction "D_3") (pintype "passive"))
    )
    (net (code "29") (name "Net-(D10-K)") (class "Default")
      (node (ref "D10") (pin "2") (pinfunction "K_2") (pintype "passive"))
      (node (ref "J94") (pin "1") (pinfunction "1_1") (pintype "passive"))
      (node (ref "J95") (pin "1") (pinfunction "1_1") (pintype "passive"))
      (node (ref "J96") (pin "1") (pinfunction "1_1") (pintype "passive"))
      (node (ref "P21") (pin "1") (pinfunction "1_1") (pintype "passive"))
    )
    (net (code "30") (name "Net-(D32-A)") (class "Default")
      (node (ref "D32") (pin "1") (pinfunction "A_1") (pintype "passive"))
      (node (ref "R76") (pin "1") (pinfunction "1_1") (pintype "passive"))
    )
    (net (code "31") (name "Net-(D33-A)") (class "Default")
      (node (ref "D33") (pin "1") (pinfunction "A_1") (pintype "passive"))
      (node (ref "R77") (pin "1") (pinfunction "1_1") (pintype "passive"))
    )
    (net (code "32") (name "Net-(D34-A)") (class "Default")
      (node (ref "D34") (pin "1") (pinfunction "A_1") (pintype "passive"))
      (node (ref "R78") (pin "1") (pinfunction "1_1") (pintype "passive"))
    )
    (net (code "33") (name "Net-(D35-A)") (class "Default")
      (node (ref "D35") (pin "1") (pinfunction "A_1") (pintype "passive"))
      (node (ref "R79") (pin "1") (pinfunction "1_1") (pintype "passive"))
    )
    (net (code "34") (name "Net-(D35-K)") (class "Default")
      (node (ref "D35") (pin "2") (pinfunction "K_2") (pintype "passive"))
      (node (ref "D8") (pin "1") (pinfunction "A_1") (pintype "passive"))
      (node (ref "P19") (pin "2") (pinfunction "2_2") (pintype "passive"))
      (node (ref "Q4") (pin "3") (pinfunction "D_3") (pintype "passive"))
    )
    (net (code "35") (name "Net-(D36-A)") (class "Default")
      (node (ref "D36") (pin "1") (pinfunction "A_1") (pintype "passive"))
      (node (ref "R80") (pin "1") (pinfunction "1_1") (pintype "passive"))
    )
    (net (code "36") (name "Net-(D36-K)") (class "Default")
      (node (ref "D36") (pin "2") (pinfunction "K_2") (pintype "passive"))
      (node (ref "D9") (pin "1") (pinfunction "A_1") (pintype "passive"))
      (node (ref "P20") (pin "2") (pinfunction "2_2") (pintype "passive"))
      (node (ref "Q5") (pin "3") (pinfunction "D_3") (pintype "passive"))
    )
    (net (code "37") (name "Net-(D37-A)") (class "Default")
      (node (ref "D37") (pin "1") (pinfunction "A_1") (pintype "passive"))
      (node (ref "R81") (pin "1") (pinfunction "1_1") (pintype "passive"))
    )
    (net (code "38") (name "Net-(D41-A)") (class "Default")
      (node (ref "D41") (pin "1") (pinfunction "A_1") (pintype "passive"))
      (node (ref "R94") (pin "2") (pinfunction "2_2") (pintype "passive"))
    )
    (net (code "39") (name "Net-(D41-K)") (class "Default")
      (node (ref "D41") (pin "2") (pinfunction "K_2") (pintype "passive"))
      (node (ref "Q30") (pin "3") (pinfunction "D_3") (pintype "passive"))
    )
    (net (code "40") (name "Net-(Q1-G)") (class "Default")
      (node (ref "Q1") (pin "1") (pinfunction "G_1") (pintype "passive"))
      (node (ref "R9") (pin "2") (pinfunction "2_2") (pintype "passive"))
    )
    (net (code "41") (name "Net-(Q2-G)") (class "Default")
      (node (ref "Q2") (pin "1") (pinfunction "G_1") (pintype "passive"))
      (node (ref "R10") (pin "2") (pinfunction "2_2") (pintype "passive"))
    )
    (net (code "42") (name "Net-(Q3-G)") (class "Default")
      (node (ref "Q3") (pin "1") (pinfunction "G_1") (pintype "passive"))
      (node (ref "R29") (pin "2") (pinfunction "2_2") (pintype "passive"))
    )
    (net (code "43") (name "Net-(Q4-G)") (class "Default")
      (node (ref "Q4") (pin "1") (pinfunction "G_1") (pintype "passive"))
      (node (ref "R20") (pin "2") (pinfunction "2_2") (pintype "passive"))
    )
    (net (code "44") (name "Net-(Q5-G)") (class "Default")
      (node (ref "Q5") (pin "1") (pinfunction "G_1") (pintype "passive"))
      (node (ref "R19") (pin "2") (pinfunction "2_2") (pintype "passive"))
    )
    (net (code "45") (name "Net-(Q6-G)") (class "Default")
      (node (ref "Q6") (pin "1") (pinfunction "G_1") (pintype "passive"))
      (node (ref "R30") (pin "2") (pinfunction "2_2") (pintype "passive"))
    )
    (net (code "46") (name "Net-(Q24-D)") (class "Default")
      (node (ref "P22") (pin "2") (pinfunction "2_2") (pintype "passive"))
      (node (ref "Q24") (pin "3") (pinfunction "D_3") (pintype "passive"))
      (node (ref "R82") (pin "1") (pinfunction "1_1") (pintype "passive"))
    )
    (net (code "47") (name "Net-(Q24-G)") (class "Default")
      (node (ref "Q24") (pin "1") (pinfunction "G_1") (pintype "passive"))
      (node (ref "R95") (pin "2") (pinfunction "2_2") (pintype "passive"))
    )
    (net (code "48") (name "Net-(Q25-D)") (class "Default")
      (node (ref "P23") (pin "2") (pinfunction "2_2") (pintype "passive"))
      (node (ref "Q25") (pin "3") (pinfunction "D_3") (pintype "passive"))
      (node (ref "R83") (pin "1") (pinfunction "1_1") (pintype "passive"))
    )
    (net (code "49") (name "Net-(Q25-G)") (class "Default")
      (node (ref "Q25") (pin "1") (pinfunction "G_1") (pintype "passive"))
      (node (ref "R97") (pin "2") (pinfunction "2_2") (pintype "passive"))
    )
    (net (code "50") (name "Net-(Q26-D)") (class "Default")
      (node (ref "P24") (pin "2") (pinfunction "2_2") (pintype "passive"))
      (node (ref "Q26") (pin "3") (pinfunction "D_3") (pintype "passive"))
      (node (ref "R84") (pin "1") (pinfunction "1_1") (pintype "passive"))
    )
    (net (code "51") (name "Net-(Q26-G)") (class "Default")
      (node (ref "Q26") (pin "1") (pinfunction "G_1") (pintype "passive"))
      (node (ref "R101") (pin "2") (pinfunction "2_2") (pintype "passive"))
    )
    (net (code "52") (name "Net-(Q27-D)") (class "Default")
      (node (ref "P25") (pin "2") (pinfunction "2_2") (pintype "passive"))
      (node (ref "Q27") (pin "3") (pinfunction "D_3") (pintype "passive"))
      (node (ref "R85") (pin "1") (pinfunction "1_1") (pintype "passive"))
    )
    (net (code "53") (name "Net-(Q27-G)") (class "Default")
      (node (ref "Q27") (pin "1") (pinfunction "G_1") (pintype "passive"))
      (node (ref "R103") (pin "2") (pinfunction "2_2") (pintype "passive"))
    )
    (net (code "54") (name "Net-(Q30-G)") (class "Default")
      (node (ref "Q30") (pin "1") (pinfunction "G_1") (pintype "passive"))
      (node (ref "R99") (pin "2") (pinfunction "2_2") (pintype "passive"))
    )
    (net (code "55") (name "Vservo") (class "Default")
      (node (ref "P22") (pin "1") (pinfunction "1_1") (pintype "passive"))
      (node (ref "P23") (pin "1") (pinfunction "1_1") (pintype "passive"))
      (node (ref "P24") (pin "1") (pinfunction "1_1") (pintype "passive"))
      (node (ref "P25") (pin "1") (pinfunction "1_1") (pintype "passive"))
    )
  )
)
